# butterfly-fc.net
KiCad netlist of a schematic drawn in EAGLE
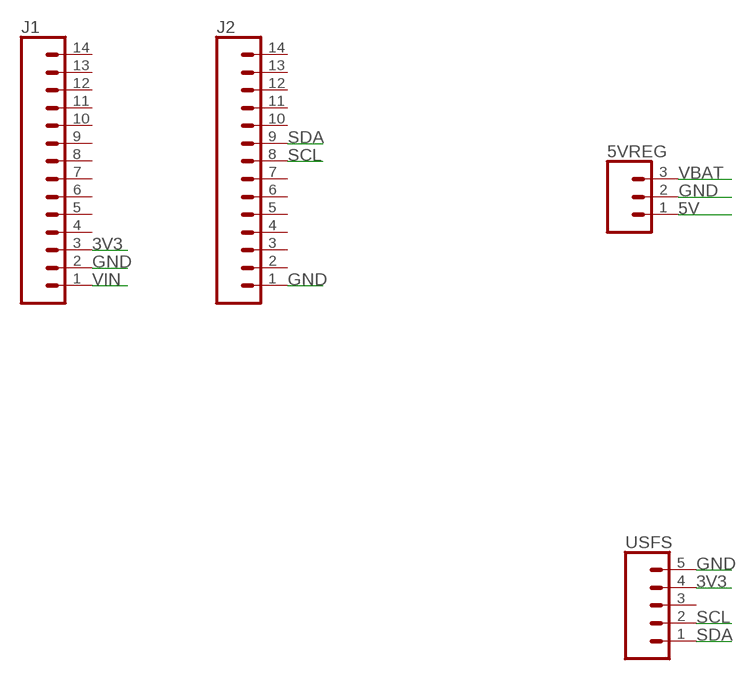
[diagram p0: schematic, sheet 1]

(export (version "E")
  (design (tool "Eeschema 10.0.6"))
  (components
    (comp (ref "5VREG")
      (value "CONN_031X03_NO_SILK")
      (footprint "eagle-import:1X03_NO_SILK")
      (libsource (lib "eagle-import") (part "CONN_031X03_NO_SILK"))
    )
    (comp (ref "J1")
      (value "CONN_14NO_SILK")
      (footprint "eagle-import:1X14_NO_SILK")
      (libsource (lib "eagle-import") (part "CONN_14NO_SILK"))
    )
    (comp (ref "J2")
      (value "CONN_14NO_SILK")
      (footprint "eagle-import:1X14_NO_SILK")
      (libsource (lib "eagle-import") (part "CONN_14NO_SILK"))
    )
    (comp (ref "USFS")
      (value "CONN_05NO_SILK")
      (footprint "eagle-import:1X05_NO_SILK")
      (libsource (lib "eagle-import") (part "CONN_05NO_SILK"))
    )
  )
  (nets
    (net (code "1") (name "/3V3") (class "Default")
      (node (ref "J1") (pin "3") (pinfunction "3_3") (pintype "passive"))
      (node (ref "USFS") (pin "4") (pinfunction "4_4") (pintype "passive"))
    )
    (net (code "2") (name "/5V") (class "Default")
      (node (ref "5VREG") (pin "1") (pinfunction "1_1") (pintype "passive"))
    )
    (net (code "3") (name "/GND") (class "Default")
      (node (ref "5VREG") (pin "2") (pinfunction "2_2") (pintype "passive"))
      (node (ref "J1") (pin "2") (pinfunction "2_2") (pintype "passive"))
      (node (ref "J2") (pin "1") (pinfunction "1_1") (pintype "passive"))
      (node (ref "USFS") (pin "5") (pinfunction "5_5") (pintype "passive"))
    )
    (net (code "4") (name "/SCL") (class "Default")
      (node (ref "J2") (pin "8") (pinfunction "8_8") (pintype "passive"))
      (node (ref "USFS") (pin "2") (pinfunction "2_2") (pintype "passive"))
    )
    (net (code "5") (name "/SDA") (class "Default")
      (node (ref "J2") (pin "9") (pinfunction "9_9") (pintype "passive"))
      (node (ref "USFS") (pin "1") (pinfunction "1_1") (pintype "passive"))
    )
    (net (code "6") (name "/VBAT") (class "Default")
      (node (ref "5VREG") (pin "3") (pinfunction "3_3") (pintype "passive"))
    )
    (net (code "7") (name "/VIN") (class "Default")
      (node (ref "J1") (pin "1") (pinfunction "1_1") (pintype "passive"))
    )
    (net (code "8") (name "unconnected-(J1-Pad4)") (class "Default")
      (node (ref "J1") (pin "4") (pinfunction "4_4") (pintype "passive"))
    )
    (net (code "9") (name "unconnected-(J1-Pad5)") (class "Default")
      (node (ref "J1") (pin "5") (pinfunction "5_5") (pintype "passive"))
    )
    (net (code "10") (name "unconnected-(J1-Pad6)") (class "Default")
      (node (ref "J1") (pin "6") (pinfunction "6_6") (pintype "passive"))
    )
    (net (code "11") (name "unconnected-(J1-Pad7)") (class "Default")
      (node (ref "J1") (pin "7") (pinfunction "7_7") (pintype "passive"))
    )
    (net (code "12") (name "unconnected-(J1-Pad8)") (class "Default")
      (node (ref "J1") (pin "8") (pinfunction "8_8") (pintype "passive"))
    )
    (net (code "13") (name "unconnected-(J1-Pad9)") (class "Default")
      (node (ref "J1") (pin "9") (pinfunction "9_9") (pintype "passive"))
    )
    (net (code "14") (name "unconnected-(J1-Pad10)") (class "Default")
      (node (ref "J1") (pin "10") (pinfunction "10_10") (pintype "passive"))
    )
    (net (code "15") (name "unconnected-(J1-Pad11)") (class "Default")
      (node (ref "J1") (pin "11") (pinfunction "11_11") (pintype "passive"))
    )
    (net (code "16") (name "unconnected-(J1-Pad12)") (class "Default")
      (node (ref "J1") (pin "12") (pinfunction "12_12") (pintype "passive"))
    )
    (net (code "17") (name "unconnected-(J1-Pad13)") (class "Default")
      (node (ref "J1") (pin "13") (pinfunction "13_13") (pintype "passive"))
    )
    (net (code "18") (name "unconnected-(J1-Pad14)") (class "Default")
      (node (ref "J1") (pin "14") (pinfunction "14_14") (pintype "passive"))
    )
    (net (code "19") (name "unconnected-(J2-Pad2)") (class "Default")
      (node (ref "J2") (pin "2") (pinfunction "2_2") (pintype "passive"))
    )
    (net (code "20") (name "unconnected-(J2-Pad3)") (class "Default")
      (node (ref "J2") (pin "3") (pinfunction "3_3") (pintype "passive"))
    )
    (net (code "21") (name "unconnected-(J2-Pad4)") (class "Default")
      (node (ref "J2") (pin "4") (pinfunction "4_4") (pintype "passive"))
    )
    (net (code "22") (name "unconnected-(J2-Pad5)") (class "Default")
      (node (ref "J2") (pin "5") (pinfunction "5_5") (pintype "passive"))
    )
    (net (code "23") (name "unconnected-(J2-Pad6)") (class "Default")
      (node (ref "J2") (pin "6") (pinfunction "6_6") (pintype "passive"))
    )
    (net (code "24") (name "unconnected-(J2-Pad7)") (class "Default")
      (node (ref "J2") (pin "7") (pinfunction "7_7") (pintype "passive"))
    )
    (net (code "25") (name "unconnected-(J2-Pad10)") (class "Default")
      (node (ref "J2") (pin "10") (pinfunction "10_10") (pintype "passive"))
    )
    (net (code "26") (name "unconnected-(J2-Pad11)") (class "Default")
      (node (ref "J2") (pin "11") (pinfunction "11_11") (pintype "passive"))
    )
    (net (code "27") (name "unconnected-(J2-Pad12)") (class "Default")
      (node (ref "J2") (pin "12") (pinfunction "12_12") (pintype "passive"))
    )
    (net (code "28") (name "unconnected-(J2-Pad13)") (class "Default")
      (node (ref "J2") (pin "13") (pinfunction "13_13") (pintype "passive"))
    )
    (net (code "29") (name "unconnected-(J2-Pad14)") (class "Default")
      (node (ref "J2") (pin "14") (pinfunction "14_14") (pintype "passive"))
    )
    (net (code "30") (name "unconnected-(USFS-Pad3)") (class "Default")
      (node (ref "USFS") (pin "3") (pinfunction "3_3") (pintype "passive"))
    )
  )
)
